# UV_exposure_v1_0.net
KiCad netlist of a schematic drawn in EAGLE
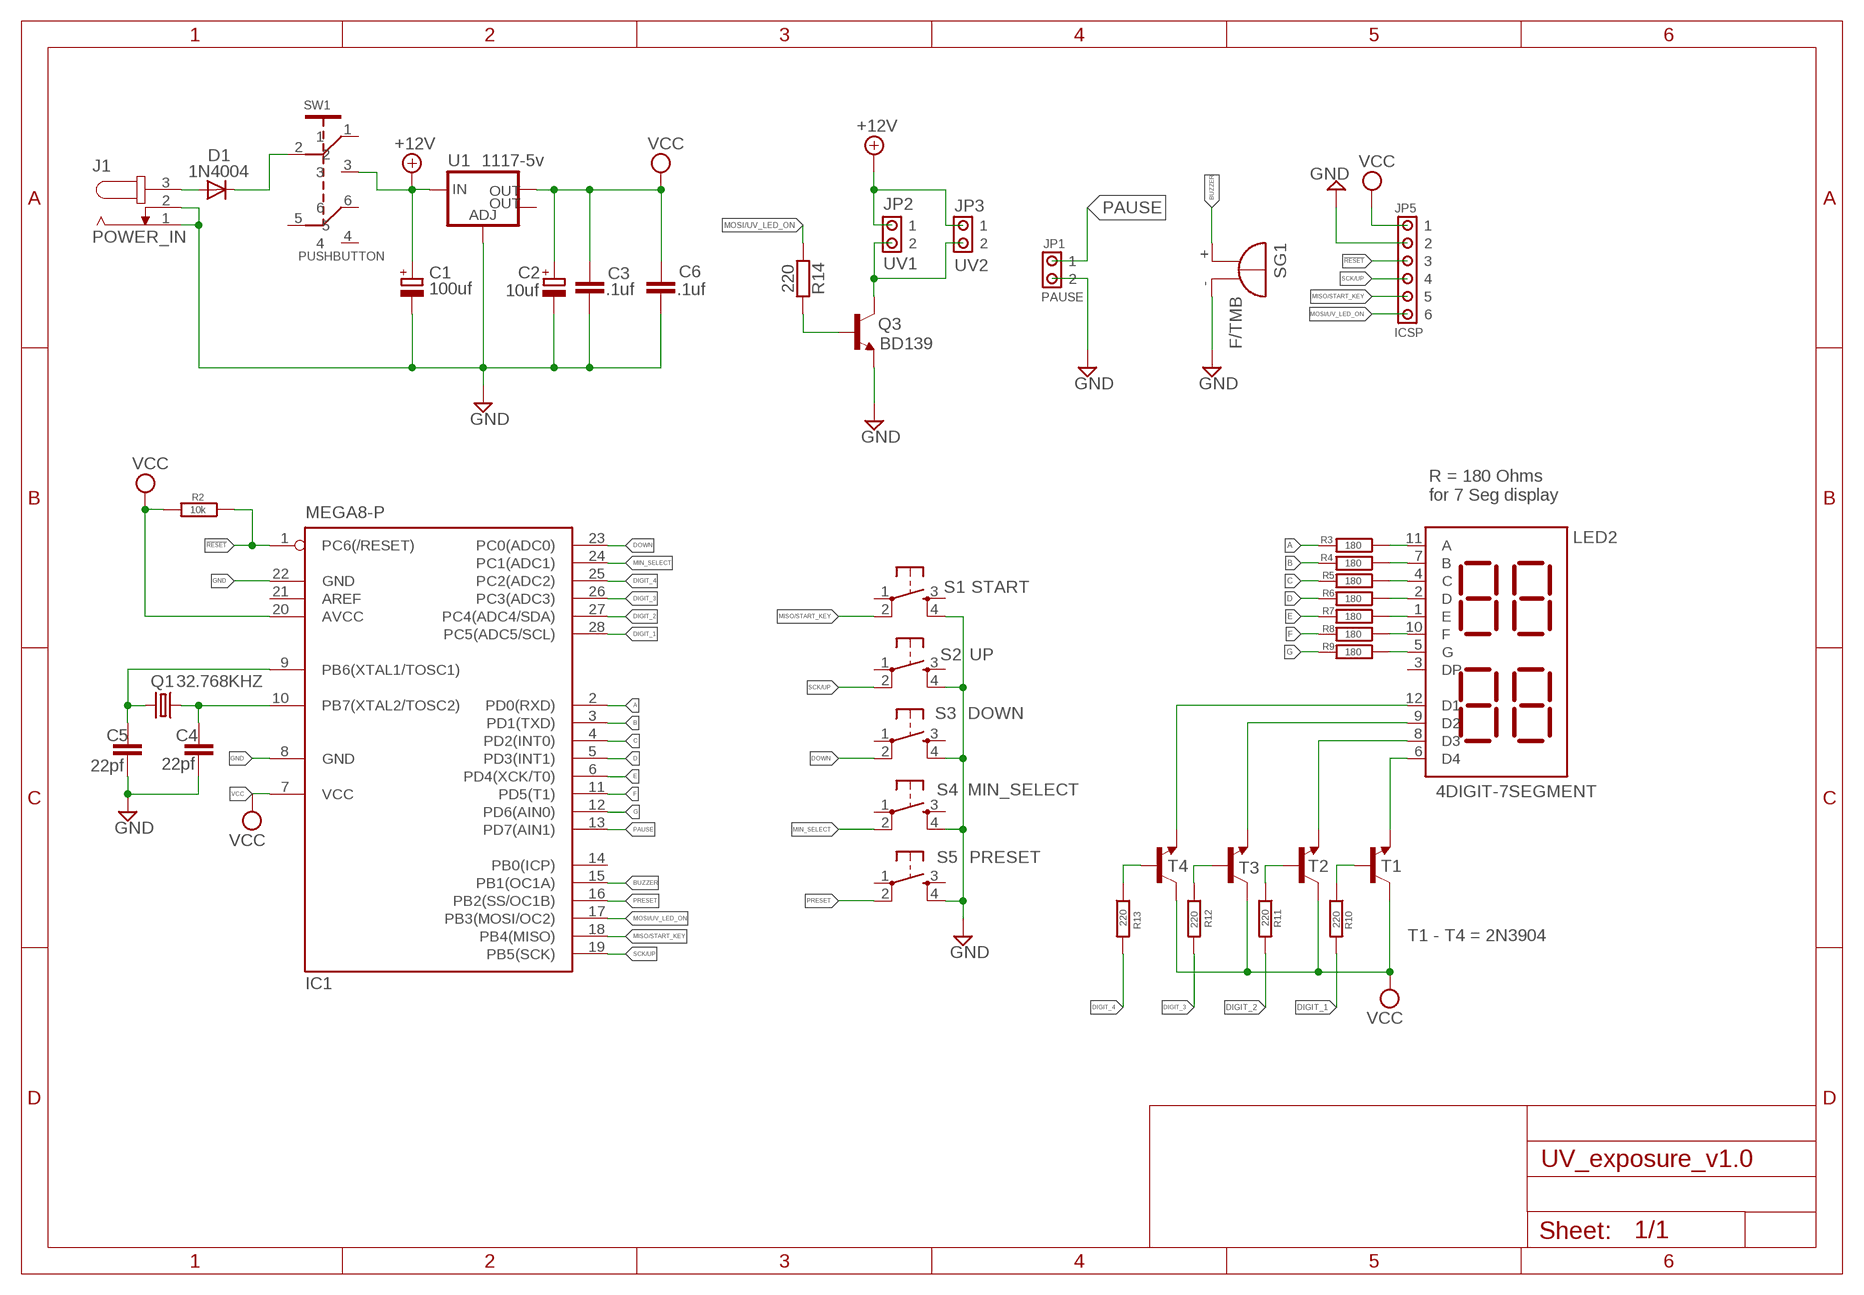
[diagram p0: schematic, sheet 1]

(export (version "E")
  (design (tool "Eeschema 10.0.6"))
  (components
    (comp (ref "C1")
      (value "100uf")
      (footprint "eagle-import:UD-6,3X7,7_NICHICON")
      (libsource (lib "eagle-import") (part "CPOL-EUUD-6,3X7,7"))
    )
    (comp (ref "C2")
      (value "10uf")
      (footprint "eagle-import:153CLV-0505")
      (libsource (lib "eagle-import") (part "CPOL-EU153CLV-0505"))
    )
    (comp (ref "C3")
      (value ".1uf")
      (footprint "eagle-import:C0805")
      (libsource (lib "eagle-import") (part "C-EUC0805"))
    )
    (comp (ref "C4")
      (value "22pf")
      (footprint "eagle-import:C0805")
      (libsource (lib "eagle-import") (part "C-EUC0805"))
    )
    (comp (ref "C5")
      (value "22pf")
      (footprint "eagle-import:C0805")
      (libsource (lib "eagle-import") (part "C-EUC0805"))
    )
    (comp (ref "C6")
      (value ".1uf")
      (footprint "eagle-import:C0805")
      (libsource (lib "eagle-import") (part "C-EUC0805"))
    )
    (comp (ref "D1")
      (value "1N4004")
      (footprint "eagle-import:DO214AA")
      (libsource (lib "eagle-import") (part "DIODE-DO214AA"))
    )
    (comp (ref "IC1")
      (value "MEGA8-P")
      (footprint "eagle-import:DIL28-3")
      (libsource (lib "eagle-import") (part "MEGA8-P"))
    )
    (comp (ref "J1")
      (value "POWER_IN")
      (footprint "eagle-import:SPC4078")
      (libsource (lib "eagle-import") (part "JACK-PLUG1"))
    )
    (comp (ref "JP1")
      (value "PAUSE")
      (footprint "eagle-import:1X2_LONG")
      (libsource (lib "eagle-import") (part "PIN_HDR_2X1{colon}{colon}LONG"))
    )
    (comp (ref "JP2")
      (value "UV1")
      (footprint "eagle-import:1X2_LONG")
      (libsource (lib "eagle-import") (part "PIN_HDR_2X1{colon}{colon}LONG"))
    )
    (comp (ref "JP3")
      (value "UV2")
      (footprint "eagle-import:1X2_LONG")
      (libsource (lib "eagle-import") (part "PIN_HDR_2X1{colon}{colon}LONG"))
    )
    (comp (ref "JP5")
      (value "ICSP")
      (footprint "eagle-import:1X6_LONG")
      (libsource (lib "eagle-import") (part "PIN_HDR_6X1"))
    )
    (comp (ref "LED2")
      (value "4DIGIT-7SEGMENT")
      (footprint "eagle-import:4DIGIT-7SEGMENT")
      (libsource (lib "eagle-import") (part "4DIGIT-7SEGMENT"))
    )
    (comp (ref "Q1")
      (value "32.768KHZ")
      (footprint "eagle-import:TC26V")
      (libsource (lib "eagle-import") (part "CRYSTALTC26V"))
    )
    (comp (ref "Q3")
      (value "BD139")
      (footprint "eagle-import:TO126")
      (libsource (lib "eagle-import") (part "BD139"))
    )
    (comp (ref "R2")
      (value "10k")
      (footprint "eagle-import:R1206W")
      (libsource (lib "eagle-import") (part "R-EU_R1206W"))
    )
    (comp (ref "R3")
      (value "180")
      (footprint "eagle-import:R1206W")
      (libsource (lib "eagle-import") (part "R-EU_R1206W"))
    )
    (comp (ref "R4")
      (value "180")
      (footprint "eagle-import:R1206W")
      (libsource (lib "eagle-import") (part "R-EU_R1206W"))
    )
    (comp (ref "R5")
      (value "180")
      (footprint "eagle-import:R1206W")
      (libsource (lib "eagle-import") (part "R-EU_R1206W"))
    )
    (comp (ref "R6")
      (value "180")
      (footprint "eagle-import:R1206W")
      (libsource (lib "eagle-import") (part "R-EU_R1206W"))
    )
    (comp (ref "R7")
      (value "180")
      (footprint "eagle-import:R1206W")
      (libsource (lib "eagle-import") (part "R-EU_R1206W"))
    )
    (comp (ref "R8")
      (value "180")
      (footprint "eagle-import:R1206W")
      (libsource (lib "eagle-import") (part "R-EU_R1206W"))
    )
    (comp (ref "R9")
      (value "180")
      (footprint "eagle-import:R1206W")
      (libsource (lib "eagle-import") (part "R-EU_R1206W"))
    )
    (comp (ref "R10")
      (value "220")
      (footprint "eagle-import:R1206W")
      (libsource (lib "eagle-import") (part "R-EU_R1206W"))
    )
    (comp (ref "R11")
      (value "220")
      (footprint "eagle-import:R1206W")
      (libsource (lib "eagle-import") (part "R-EU_R1206W"))
    )
    (comp (ref "R12")
      (value "220")
      (footprint "eagle-import:R1206W")
      (libsource (lib "eagle-import") (part "R-EU_R1206W"))
    )
    (comp (ref "R13")
      (value "220")
      (footprint "eagle-import:R1206W")
      (libsource (lib "eagle-import") (part "R-EU_R1206W"))
    )
    (comp (ref "R14")
      (value "220")
      (footprint "eagle-import:R1206W")
      (libsource (lib "eagle-import") (part "R-EU_R1206W"))
    )
    (comp (ref "S1")
      (value "START")
      (footprint "eagle-import:B3F-10XX")
      (libsource (lib "eagle-import") (part "10-XX-SWITCH"))
    )
    (comp (ref "S2")
      (value "UP")
      (footprint "eagle-import:B3F-10XX")
      (libsource (lib "eagle-import") (part "10-XX-SWITCH"))
    )
    (comp (ref "S3")
      (value "DOWN")
      (footprint "eagle-import:B3F-10XX")
      (libsource (lib "eagle-import") (part "10-XX-SWITCH"))
    )
    (comp (ref "S4")
      (value "MIN_SELECT")
      (footprint "eagle-import:B3F-10XX")
      (libsource (lib "eagle-import") (part "10-XX-SWITCH"))
    )
    (comp (ref "S5")
      (value "PRESET")
      (footprint "eagle-import:B3F-10XX")
      (libsource (lib "eagle-import") (part "10-XX-SWITCH"))
    )
    (comp (ref "SG1")
      (value "F/TMB")
      (footprint "eagle-import:F_TMB")
      (libsource (lib "eagle-import") (part "F/TMB"))
    )
    (comp (ref "SW1")
      (value "PUSHBUTTON")
      (footprint "eagle-import:SPDT-6PIN")
      (libsource (lib "eagle-import") (part "PUSHBUTTON"))
    )
    (comp (ref "T1")
      (value "2N3904")
      (footprint "eagle-import:SOT23-BEC")
      (libsource (lib "eagle-import") (part "-NPN-SOT23-BECMMBT3904LT1"))
    )
    (comp (ref "T2")
      (value "2N3904")
      (footprint "eagle-import:SOT23-BEC")
      (libsource (lib "eagle-import") (part "-NPN-SOT23-BECMMBT3904LT1"))
    )
    (comp (ref "T3")
      (value "2N3904")
      (footprint "eagle-import:SOT23-BEC")
      (libsource (lib "eagle-import") (part "-NPN-SOT23-BECMMBT3904LT1"))
    )
    (comp (ref "T4")
      (value "2N3904")
      (footprint "eagle-import:SOT23-BEC")
      (libsource (lib "eagle-import") (part "-NPN-SOT23-BECMMBT3904LT1"))
    )
    (comp (ref "U1")
      (value "1117-5v")
      (footprint "eagle-import:SOT223")
      (libsource (lib "eagle-import") (part "V_REG_LM1117SOT223"))
    )
  )
  (nets
    (net (code "1") (name "+12V") (class "Default")
      (node (ref "C1") (pin "+") (pinfunction "+_+") (pintype "passive"))
      (node (ref "JP2") (pin "1") (pinfunction "1_1") (pintype "passive"))
      (node (ref "JP3") (pin "1") (pinfunction "1_1") (pintype "passive"))
      (node (ref "SW1") (pin "3") (pinfunction "3_3") (pintype "passive"))
      (node (ref "U1") (pin "3") (pinfunction "IN_3") (pintype "input"))
    )
    (net (code "2") (name "/~{RESET}") (class "Default")
      (node (ref "IC1") (pin "1") (pinfunction "PC6(/RESET)_1") (pintype "bidirectional"))
      (node (ref "JP5") (pin "3") (pinfunction "3_3") (pintype "passive"))
      (node (ref "R2") (pin "1") (pinfunction "1_1") (pintype "passive"))
    )
    (net (code "3") (name "A") (class "Default")
      (node (ref "IC1") (pin "2") (pinfunction "PD0(RXD)_2") (pintype "bidirectional"))
      (node (ref "R3") (pin "2") (pinfunction "2_2") (pintype "passive"))
    )
    (net (code "4") (name "B") (class "Default")
      (node (ref "IC1") (pin "3") (pinfunction "PD1(TXD)_3") (pintype "bidirectional"))
      (node (ref "R4") (pin "2") (pinfunction "2_2") (pintype "passive"))
    )
    (net (code "5") (name "BUZZER") (class "Default")
      (node (ref "IC1") (pin "15") (pinfunction "PB1(OC1A)_15") (pintype "bidirectional"))
      (node (ref "SG1") (pin "+") (pinfunction "+_+") (pintype "passive"))
    )
    (net (code "6") (name "C") (class "Default")
      (node (ref "IC1") (pin "4") (pinfunction "PD2(INT0)_4") (pintype "bidirectional"))
      (node (ref "R5") (pin "2") (pinfunction "2_2") (pintype "passive"))
    )
    (net (code "7") (name "D") (class "Default")
      (node (ref "IC1") (pin "5") (pinfunction "PD3(INT1)_5") (pintype "bidirectional"))
      (node (ref "R6") (pin "2") (pinfunction "2_2") (pintype "passive"))
    )
    (net (code "8") (name "DIGIT_1") (class "Default")
      (node (ref "IC1") (pin "28") (pinfunction "PC5(ADC5/SCL)_28") (pintype "bidirectional"))
      (node (ref "R10") (pin "2") (pinfunction "2_2") (pintype "passive"))
    )
    (net (code "9") (name "DIGIT_2") (class "Default")
      (node (ref "IC1") (pin "27") (pinfunction "PC4(ADC4/SDA)_27") (pintype "bidirectional"))
      (node (ref "R11") (pin "2") (pinfunction "2_2") (pintype "passive"))
    )
    (net (code "10") (name "DIGIT_3") (class "Default")
      (node (ref "IC1") (pin "26") (pinfunction "PC3(ADC3)_26") (pintype "bidirectional"))
      (node (ref "R12") (pin "2") (pinfunction "2_2") (pintype "passive"))
    )
    (net (code "11") (name "DIGIT_4") (class "Default")
      (node (ref "IC1") (pin "25") (pinfunction "PC2(ADC2)_25") (pintype "bidirectional"))
      (node (ref "R13") (pin "2") (pinfunction "2_2") (pintype "passive"))
    )
    (net (code "12") (name "DOWN") (class "Default")
      (node (ref "IC1") (pin "23") (pinfunction "PC0(ADC0)_23") (pintype "bidirectional"))
      (node (ref "S3") (pin "2") (pinfunction "P1_2") (pintype "passive"))
    )
    (net (code "13") (name "E") (class "Default")
      (node (ref "IC1") (pin "6") (pinfunction "PD4(XCK/T0)_6") (pintype "bidirectional"))
      (node (ref "R7") (pin "2") (pinfunction "2_2") (pintype "passive"))
    )
    (net (code "14") (name "F") (class "Default")
      (node (ref "IC1") (pin "11") (pinfunction "PD5(T1)_11") (pintype "bidirectional"))
      (node (ref "R8") (pin "2") (pinfunction "2_2") (pintype "passive"))
    )
    (net (code "15") (name "G") (class "Default")
      (node (ref "IC1") (pin "12") (pinfunction "PD6(AIN0)_12") (pintype "bidirectional"))
      (node (ref "R9") (pin "2") (pinfunction "2_2") (pintype "passive"))
    )
    (net (code "16") (name "GND") (class "Default")
      (node (ref "C1") (pin "-") (pinfunction "-_-") (pintype "passive"))
      (node (ref "C2") (pin "-") (pinfunction "-_-") (pintype "passive"))
      (node (ref "C3") (pin "2") (pinfunction "2_2") (pintype "passive"))
      (node (ref "C4") (pin "2") (pinfunction "2_2") (pintype "passive"))
      (node (ref "C5") (pin "2") (pinfunction "2_2") (pintype "passive"))
      (node (ref "C6") (pin "2") (pinfunction "2_2") (pintype "passive"))
      (node (ref "IC1") (pin "22") (pinfunction "GND_22") (pintype "power_in"))
      (node (ref "IC1") (pin "8") (pinfunction "GND_8") (pintype "power_in"))
      (node (ref "J1") (pin "1") (pinfunction "1_1") (pintype "passive"))
      (node (ref "J1") (pin "2") (pinfunction "2_2") (pintype "passive"))
      (node (ref "JP1") (pin "2") (pinfunction "2_2") (pintype "passive"))
      (node (ref "JP5") (pin "2") (pinfunction "2_2") (pintype "passive"))
      (node (ref "Q3") (pin "1") (pinfunction "E_1") (pintype "passive"))
      (node (ref "S1") (pin "4") (pinfunction "S1_4") (pintype "passive"))
      (node (ref "S2") (pin "4") (pinfunction "S1_4") (pintype "passive"))
      (node (ref "S3") (pin "4") (pinfunction "S1_4") (pintype "passive"))
      (node (ref "S4") (pin "4") (pinfunction "S1_4") (pintype "passive"))
      (node (ref "S5") (pin "4") (pinfunction "S1_4") (pintype "passive"))
      (node (ref "SG1") (pin "-") (pinfunction "-_-") (pintype "passive"))
      (node (ref "U1") (pin "1") (pinfunction "ADJ_1") (pintype "input"))
    )
    (net (code "17") (name "MIN_SELECT") (class "Default")
      (node (ref "IC1") (pin "24") (pinfunction "PC1(ADC1)_24") (pintype "bidirectional"))
      (node (ref "S4") (pin "2") (pinfunction "P1_2") (pintype "passive"))
    )
    (net (code "18") (name "MISO{slash}START_KEY") (class "Default")
      (node (ref "IC1") (pin "18") (pinfunction "PB4(MISO)_18") (pintype "bidirectional"))
      (node (ref "JP5") (pin "5") (pinfunction "5_5") (pintype "passive"))
      (node (ref "S1") (pin "2") (pinfunction "P1_2") (pintype "passive"))
    )
    (net (code "19") (name "MOSI{slash}UV_LED_ON") (class "Default")
      (node (ref "IC1") (pin "17") (pinfunction "PB3(MOSI/OC2)_17") (pintype "bidirectional"))
      (node (ref "JP5") (pin "6") (pinfunction "6_6") (pintype "passive"))
      (node (ref "R14") (pin "2") (pinfunction "2_2") (pintype "passive"))
    )
    (net (code "20") (name "Net-(D1-PadA)") (class "Default")
      (node (ref "D1") (pin "A") (pinfunction "A_A") (pintype "passive"))
      (node (ref "J1") (pin "3") (pinfunction "3_3") (pintype "passive"))
    )
    (net (code "21") (name "Net-(D1-PadC)") (class "Default")
      (node (ref "D1") (pin "C") (pinfunction "C_C") (pintype "passive"))
      (node (ref "SW1") (pin "2") (pinfunction "2_2") (pintype "passive"))
    )
    (net (code "22") (name "Net-(IC1-PB6(XTAL1{slash}TOSC1))") (class "Default")
      (node (ref "C5") (pin "1") (pinfunction "1_1") (pintype "passive"))
      (node (ref "IC1") (pin "9") (pinfunction "PB6(XTAL1/TOSC1)_9") (pintype "bidirectional"))
      (node (ref "Q1") (pin "2") (pinfunction "2_2") (pintype "passive"))
    )
    (net (code "23") (name "Net-(IC1-PB7(XTAL2{slash}TOSC2))") (class "Default")
      (node (ref "C4") (pin "1") (pinfunction "1_1") (pintype "passive"))
      (node (ref "IC1") (pin "10") (pinfunction "PB7(XTAL2/TOSC2)_10") (pintype "bidirectional"))
      (node (ref "Q1") (pin "1") (pinfunction "1_1") (pintype "passive"))
    )
    (net (code "24") (name "Net-(LED2-A)") (class "Default")
      (node (ref "LED2") (pin "11") (pinfunction "A_11") (pintype "passive"))
      (node (ref "R3") (pin "1") (pinfunction "1_1") (pintype "passive"))
    )
    (net (code "25") (name "Net-(LED2-B)") (class "Default")
      (node (ref "LED2") (pin "7") (pinfunction "B_7") (pintype "passive"))
      (node (ref "R4") (pin "1") (pinfunction "1_1") (pintype "passive"))
    )
    (net (code "26") (name "Net-(LED2-C)") (class "Default")
      (node (ref "LED2") (pin "4") (pinfunction "C_4") (pintype "passive"))
      (node (ref "R5") (pin "1") (pinfunction "1_1") (pintype "passive"))
    )
    (net (code "27") (name "Net-(LED2-D)") (class "Default")
      (node (ref "LED2") (pin "2") (pinfunction "D_2") (pintype "passive"))
      (node (ref "R6") (pin "1") (pinfunction "1_1") (pintype "passive"))
    )
    (net (code "28") (name "Net-(LED2-D1)") (class "Default")
      (node (ref "LED2") (pin "12") (pinfunction "D1_12") (pintype "passive"))
      (node (ref "T4") (pin "E") (pinfunction "E_E") (pintype "passive"))
    )
    (net (code "29") (name "Net-(LED2-D2)") (class "Default")
      (node (ref "LED2") (pin "9") (pinfunction "D2_9") (pintype "passive"))
      (node (ref "T3") (pin "E") (pinfunction "E_E") (pintype "passive"))
    )
    (net (code "30") (name "Net-(LED2-D3)") (class "Default")
      (node (ref "LED2") (pin "8") (pinfunction "D3_8") (pintype "passive"))
      (node (ref "T2") (pin "E") (pinfunction "E_E") (pintype "passive"))
    )
    (net (code "31") (name "Net-(LED2-D4)") (class "Default")
      (node (ref "LED2") (pin "6") (pinfunction "D4_6") (pintype "passive"))
      (node (ref "T1") (pin "E") (pinfunction "E_E") (pintype "passive"))
    )
    (net (code "32") (name "Net-(LED2-E)") (class "Default")
      (node (ref "LED2") (pin "1") (pinfunction "E_1") (pintype "passive"))
      (node (ref "R7") (pin "1") (pinfunction "1_1") (pintype "passive"))
    )
    (net (code "33") (name "Net-(LED2-F)") (class "Default")
      (node (ref "LED2") (pin "10") (pinfunction "F_10") (pintype "passive"))
      (node (ref "R8") (pin "1") (pinfunction "1_1") (pintype "passive"))
    )
    (net (code "34") (name "Net-(LED2-G)") (class "Default")
      (node (ref "LED2") (pin "5") (pinfunction "G_5") (pintype "passive"))
      (node (ref "R9") (pin "1") (pinfunction "1_1") (pintype "passive"))
    )
    (net (code "35") (name "Net-(Q3-B)") (class "Default")
      (node (ref "Q3") (pin "3") (pinfunction "B_3") (pintype "passive"))
      (node (ref "R14") (pin "1") (pinfunction "1_1") (pintype "passive"))
    )
    (net (code "36") (name "Net-(Q3-C)") (class "Default")
      (node (ref "JP2") (pin "2") (pinfunction "2_2") (pintype "passive"))
      (node (ref "JP3") (pin "2") (pinfunction "2_2") (pintype "passive"))
      (node (ref "Q3") (pin "2") (pinfunction "C_2") (pintype "passive"))
    )
    (net (code "37") (name "Net-(R10-Pad1)") (class "Default")
      (node (ref "R10") (pin "1") (pinfunction "1_1") (pintype "passive"))
      (node (ref "T1") (pin "B") (pinfunction "B_B") (pintype "passive"))
    )
    (net (code "38") (name "Net-(R11-Pad1)") (class "Default")
      (node (ref "R11") (pin "1") (pinfunction "1_1") (pintype "passive"))
      (node (ref "T2") (pin "B") (pinfunction "B_B") (pintype "passive"))
    )
    (net (code "39") (name "Net-(R12-Pad1)") (class "Default")
      (node (ref "R12") (pin "1") (pinfunction "1_1") (pintype "passive"))
      (node (ref "T3") (pin "B") (pinfunction "B_B") (pintype "passive"))
    )
    (net (code "40") (name "Net-(R13-Pad1)") (class "Default")
      (node (ref "R13") (pin "1") (pinfunction "1_1") (pintype "passive"))
      (node (ref "T4") (pin "B") (pinfunction "B_B") (pintype "passive"))
    )
    (net (code "41") (name "PAUSE") (class "Default")
      (node (ref "IC1") (pin "13") (pinfunction "PD7(AIN1)_13") (pintype "bidirectional"))
      (node (ref "JP1") (pin "1") (pinfunction "1_1") (pintype "passive"))
    )
    (net (code "42") (name "PRESET") (class "Default")
      (node (ref "IC1") (pin "16") (pinfunction "PB2(SS/OC1B)_16") (pintype "bidirectional"))
      (node (ref "S5") (pin "2") (pinfunction "P1_2") (pintype "passive"))
    )
    (net (code "43") (name "SCK{slash}UP") (class "Default")
      (node (ref "IC1") (pin "19") (pinfunction "PB5(SCK)_19") (pintype "bidirectional"))
      (node (ref "JP5") (pin "4") (pinfunction "4_4") (pintype "passive"))
      (node (ref "S2") (pin "2") (pinfunction "P1_2") (pintype "passive"))
    )
    (net (code "44") (name "VCC") (class "Default")
      (node (ref "C2") (pin "+") (pinfunction "+_+") (pintype "passive"))
      (node (ref "C3") (pin "1") (pinfunction "1_1") (pintype "passive"))
      (node (ref "C6") (pin "1") (pinfunction "1_1") (pintype "passive"))
      (node (ref "IC1") (pin "20") (pinfunction "AVCC_20") (pintype "power_in"))
      (node (ref "IC1") (pin "7") (pinfunction "VCC_7") (pintype "power_in"))
      (node (ref "JP5") (pin "1") (pinfunction "1_1") (pintype "passive"))
      (node (ref "R2") (pin "2") (pinfunction "2_2") (pintype "passive"))
      (node (ref "T1") (pin "C") (pinfunction "C_C") (pintype "passive"))
      (node (ref "T2") (pin "C") (pinfunction "C_C") (pintype "passive"))
      (node (ref "T3") (pin "C") (pinfunction "C_C") (pintype "passive"))
      (node (ref "T4") (pin "C") (pinfunction "C_C") (pintype "passive"))
      (node (ref "U1") (pin "2") (pinfunction "OUT_2") (pintype "passive"))
    )
    (net (code "45") (name "unconnected-(IC1-AREF-Pad21)") (class "Default")
      (node (ref "IC1") (pin "21") (pinfunction "AREF_21") (pintype "passive"))
    )
    (net (code "46") (name "unconnected-(IC1-PB0(ICP)-Pad14)") (class "Default")
      (node (ref "IC1") (pin "14") (pinfunction "PB0(ICP)_14") (pintype "bidirectional"))
    )
    (net (code "47") (name "unconnected-(LED2-DP-Pad3)") (class "Default")
      (node (ref "LED2") (pin "3") (pinfunction "DP_3") (pintype "passive"))
    )
    (net (code "48") (name "unconnected-(S1-P-Pad1)") (class "Default")
      (node (ref "S1") (pin "1") (pinfunction "P_1") (pintype "passive"))
    )
    (net (code "49") (name "unconnected-(S1-S-Pad3)") (class "Default")
      (node (ref "S1") (pin "3") (pinfunction "S_3") (pintype "passive"))
    )
    (net (code "50") (name "unconnected-(S2-P-Pad1)") (class "Default")
      (node (ref "S2") (pin "1") (pinfunction "P_1") (pintype "passive"))
    )
    (net (code "51") (name "unconnected-(S2-S-Pad3)") (class "Default")
      (node (ref "S2") (pin "3") (pinfunction "S_3") (pintype "passive"))
    )
    (net (code "52") (name "unconnected-(S3-P-Pad1)") (class "Default")
      (node (ref "S3") (pin "1") (pinfunction "P_1") (pintype "passive"))
    )
    (net (code "53") (name "unconnected-(S3-S-Pad3)") (class "Default")
      (node (ref "S3") (pin "3") (pinfunction "S_3") (pintype "passive"))
    )
    (net (code "54") (name "unconnected-(S4-P-Pad1)") (class "Default")
      (node (ref "S4") (pin "1") (pinfunction "P_1") (pintype "passive"))
    )
    (net (code "55") (name "unconnected-(S4-S-Pad3)") (class "Default")
      (node (ref "S4") (pin "3") (pinfunction "S_3") (pintype "passive"))
    )
    (net (code "56") (name "unconnected-(S5-P-Pad1)") (class "Default")
      (node (ref "S5") (pin "1") (pinfunction "P_1") (pintype "passive"))
    )
    (net (code "57") (name "unconnected-(S5-S-Pad3)") (class "Default")
      (node (ref "S5") (pin "3") (pinfunction "S_3") (pintype "passive"))
    )
    (net (code "58") (name "unconnected-(SW1-Pad1)") (class "Default")
      (node (ref "SW1") (pin "1") (pinfunction "1_1") (pintype "passive"))
    )
    (net (code "59") (name "unconnected-(SW1-Pad4)") (class "Default")
      (node (ref "SW1") (pin "4") (pinfunction "4_4") (pintype "passive"))
    )
    (net (code "60") (name "unconnected-(SW1-Pad5)") (class "Default")
      (node (ref "SW1") (pin "5") (pinfunction "5_5") (pintype "passive"))
    )
    (net (code "61") (name "unconnected-(SW1-Pad6)") (class "Default")
      (node (ref "SW1") (pin "6") (pinfunction "6_6") (pintype "passive"))
    )
    (net (code "62") (name "unconnected-(U1-OUT-Pad4)") (class "Default")
      (node (ref "U1") (pin "4") (pinfunction "OUT_4") (pintype "passive"))
    )
  )
)
